# LED_ring.net
KiCad netlist of a schematic drawn in Altium Designer
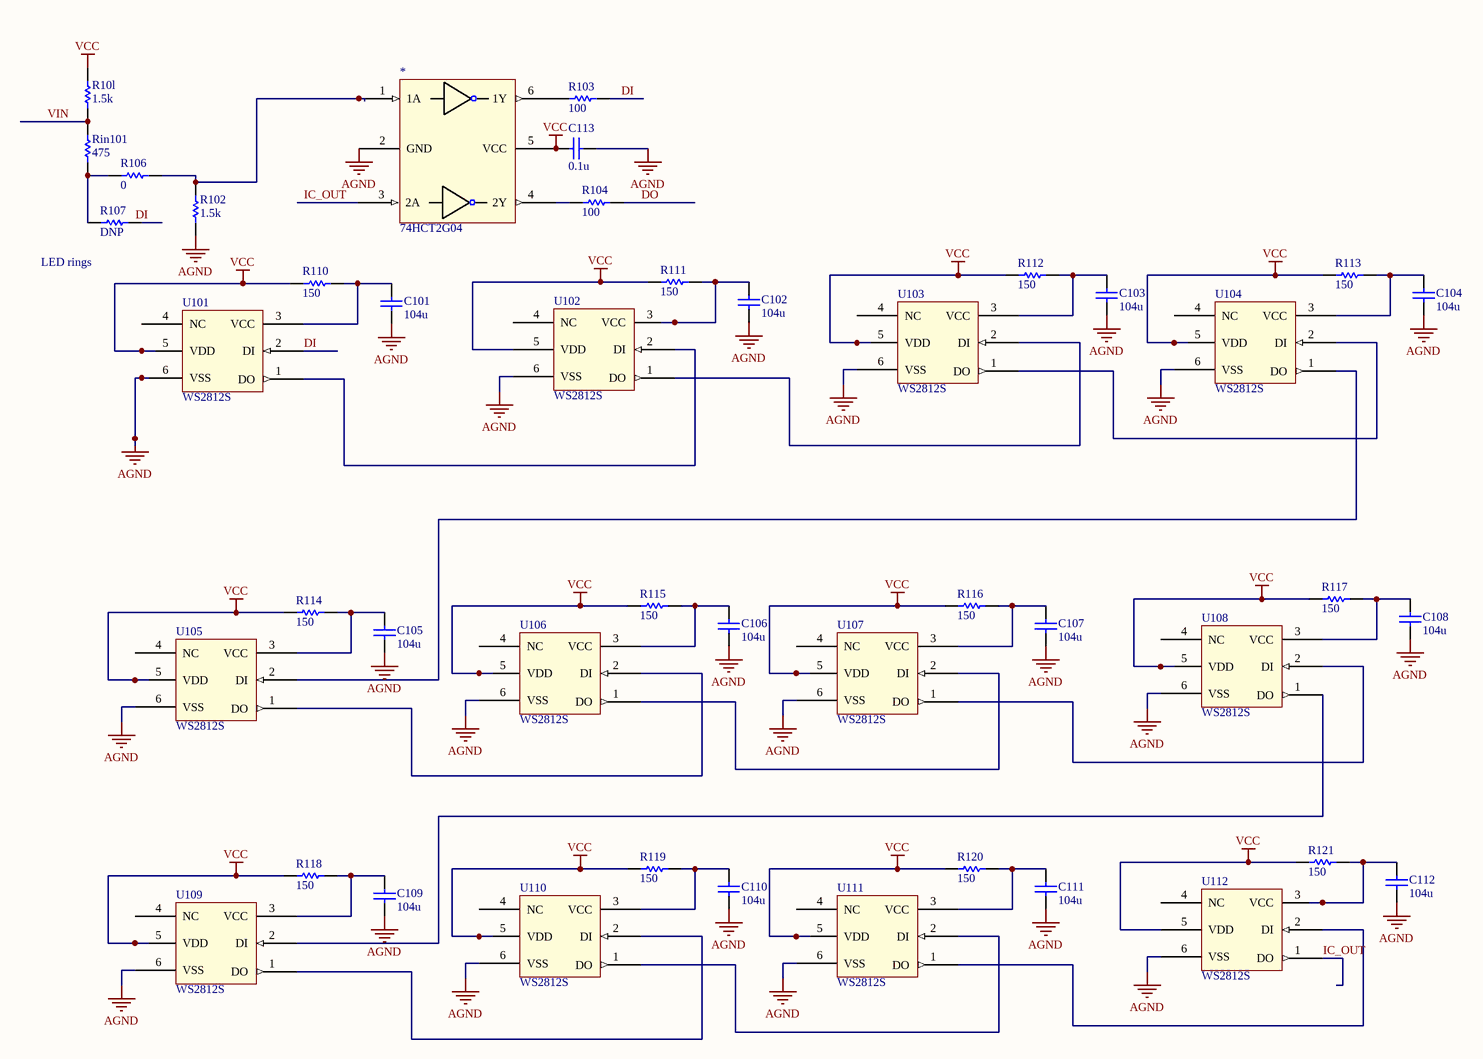
[diagram p0: LED_ring.SchDoc]

(export (version "E")
  (design (tool "Eeschema 10.0.6"))
  (components
    (comp (ref "*")
      (value "74HCT2G04")
      (footprint "SOT363-6M")
      (description "Dual inverter The 74HC2G04; 74HCT2G04 is a high-speed Si-gate CMOS device.")
      (libsource (lib "Hello") (part "74HCT2G04"))
    )
    (comp (ref "C101")
      (value "104u")
      (footprint "CAP0603_SENSE_DVT")
      (description "Chip capacitor")
      (fields (field (name "TOLERANCE") "10%") (field (name "VOLTAGE") "6.3V"))
      (libsource (lib "Hello") (part "C_10u_10_6.3_X5R_0603"))
    )
    (comp (ref "C102")
      (value "104u")
      (footprint "CAP0603_SENSE_DVT")
      (description "Chip capacitor")
      (fields (field (name "TOLERANCE") "10%") (field (name "VOLTAGE") "6.3V"))
      (libsource (lib "Hello") (part "C_10u_10_6.3_X5R_0603"))
    )
    (comp (ref "C103")
      (value "104u")
      (footprint "CAP0603_SENSE_DVT")
      (description "Chip capacitor")
      (fields (field (name "TOLERANCE") "10%") (field (name "VOLTAGE") "6.3V"))
      (libsource (lib "Hello") (part "C_10u_10_6.3_X5R_0603"))
    )
    (comp (ref "C104")
      (value "104u")
      (footprint "CAP0603_SENSE_DVT")
      (description "Chip capacitor")
      (fields (field (name "TOLERANCE") "10%") (field (name "VOLTAGE") "6.3V"))
      (libsource (lib "Hello") (part "C_10u_10_6.3_X5R_0603"))
    )
    (comp (ref "C105")
      (value "104u")
      (footprint "CAP0603_SENSE_DVT")
      (description "Chip capacitor")
      (fields (field (name "TOLERANCE") "10%") (field (name "VOLTAGE") "6.3V"))
      (libsource (lib "Hello") (part "C_10u_10_6.3_X5R_0603"))
    )
    (comp (ref "C106")
      (value "104u")
      (footprint "CAP0603_SENSE_DVT")
      (description "Chip capacitor")
      (fields (field (name "TOLERANCE") "10%") (field (name "VOLTAGE") "6.3V"))
      (libsource (lib "Hello") (part "C_10u_10_6.3_X5R_0603"))
    )
    (comp (ref "C107")
      (value "104u")
      (footprint "CAP0603_SENSE_DVT")
      (description "Chip capacitor")
      (fields (field (name "TOLERANCE") "10%") (field (name "VOLTAGE") "6.3V"))
      (libsource (lib "Hello") (part "C_10u_10_6.3_X5R_0603"))
    )
    (comp (ref "C108")
      (value "104u")
      (footprint "CAP0603_SENSE_DVT")
      (description "Chip capacitor")
      (fields (field (name "TOLERANCE") "10%") (field (name "VOLTAGE") "6.3V"))
      (libsource (lib "Hello") (part "C_10u_10_6.3_X5R_0603"))
    )
    (comp (ref "C109")
      (value "104u")
      (footprint "CAP0603_SENSE_DVT")
      (description "Chip capacitor")
      (fields (field (name "TOLERANCE") "10%") (field (name "VOLTAGE") "6.3V"))
      (libsource (lib "Hello") (part "C_10u_10_6.3_X5R_0603"))
    )
    (comp (ref "C110")
      (value "104u")
      (footprint "CAP0603_SENSE_DVT")
      (description "Chip capacitor")
      (fields (field (name "TOLERANCE") "10%") (field (name "VOLTAGE") "6.3V"))
      (libsource (lib "Hello") (part "C_10u_10_6.3_X5R_0603"))
    )
    (comp (ref "C111")
      (value "104u")
      (footprint "CAP0603_SENSE_DVT")
      (description "Chip capacitor")
      (fields (field (name "TOLERANCE") "10%") (field (name "VOLTAGE") "6.3V"))
      (libsource (lib "Hello") (part "C_10u_10_6.3_X5R_0603"))
    )
    (comp (ref "C112")
      (value "104u")
      (footprint "CAP0603_SENSE_DVT")
      (description "Chip capacitor")
      (fields (field (name "TOLERANCE") "10%") (field (name "VOLTAGE") "6.3V"))
      (libsource (lib "Hello") (part "C_10u_10_6.3_X5R_0603"))
    )
    (comp (ref "C113")
      (value "0.1u")
      (footprint "CAP0402_SENSE_DVT")
      (description "Chip capacitor")
      (fields (field (name "TOLERANCE") "10%") (field (name "VOLTAGE") "50V"))
      (libsource (lib "Hello") (part "C_0.1u_10_50_X7R_0402"))
    )
    (comp (ref "R10l")
      (value "1.5k")
      (footprint "RES0402_SENSE_DVT")
      (description "Chip Resistor")
      (fields (field (name "TOLERANCE") "5 %") (field (name "POWER") "0.1 W"))
      (libsource (lib "Hello") (part "R_1.5k_5_0.1_0402"))
    )
    (comp (ref "R102")
      (value "1.5k")
      (footprint "RES0402_SENSE_DVT")
      (description "Chip Resistor")
      (fields (field (name "TOLERANCE") "5 %") (field (name "POWER") "0.1 W"))
      (libsource (lib "Hello") (part "R_1.5k_5_0.1_0402"))
    )
    (comp (ref "R103")
      (value "100")
      (footprint "RES0402_SENSE_DVT")
      (description "Chip Resistor")
      (fields (field (name "TOLERANCE") "1 %") (field (name "POWER") "0.1 W"))
      (libsource (lib "Hello") (part "R_100_1_0.1_0402"))
    )
    (comp (ref "R104")
      (value "100")
      (footprint "RES0402_SENSE_DVT")
      (description "Chip Resistor")
      (fields (field (name "TOLERANCE") "1 %") (field (name "POWER") "0.1 W"))
      (libsource (lib "Hello") (part "R_100_1_0.1_0402"))
    )
    (comp (ref "R106")
      (value "0")
      (footprint "RES0402_SENSE_DVT")
      (description "Chip Resistor")
      (fields (field (name "TOLERANCE") "Jumper") (field (name "POWER") "0.1 W"))
      (libsource (lib "Hello") (part "R_0_jumper_0.1_0402"))
    )
    (comp (ref "R107")
      (value "DNP")
      (footprint "RES0402_SENSE_DVT")
      (description "Chip Resistor")
      (fields (field (name "TOLERANCE") "Jumper") (field (name "POWER") "0.1 W"))
      (libsource (lib "Hello") (part "R_0_jumper_0.1_0402"))
    )
    (comp (ref "R110")
      (value "150")
      (footprint "RES0402_SENSE_DVT")
      (description "Chip Resistor")
      (fields (field (name "TOLERANCE") "1 %") (field (name "POWER") "0.1 W"))
      (libsource (lib "Hello") (part "R_150_1_0.1_0402"))
    )
    (comp (ref "R111")
      (value "150")
      (footprint "RES0402_SENSE_DVT")
      (description "Chip Resistor")
      (fields (field (name "TOLERANCE") "1 %") (field (name "POWER") "0.1 W"))
      (libsource (lib "Hello") (part "R_150_1_0.1_0402"))
    )
    (comp (ref "R112")
      (value "150")
      (footprint "RES0402_SENSE_DVT")
      (description "Chip Resistor")
      (fields (field (name "TOLERANCE") "1 %") (field (name "POWER") "0.1 W"))
      (libsource (lib "Hello") (part "R_150_1_0.1_0402"))
    )
    (comp (ref "R113")
      (value "150")
      (footprint "RES0402_SENSE_DVT")
      (description "Chip Resistor")
      (fields (field (name "TOLERANCE") "1 %") (field (name "POWER") "0.1 W"))
      (libsource (lib "Hello") (part "R_150_1_0.1_0402"))
    )
    (comp (ref "R114")
      (value "150")
      (footprint "RES0402_SENSE_DVT")
      (description "Chip Resistor")
      (fields (field (name "TOLERANCE") "1 %") (field (name "POWER") "0.1 W"))
      (libsource (lib "Hello") (part "R_150_1_0.1_0402"))
    )
    (comp (ref "R115")
      (value "150")
      (footprint "RES0402_SENSE_DVT")
      (description "Chip Resistor")
      (fields (field (name "TOLERANCE") "1 %") (field (name "POWER") "0.1 W"))
      (libsource (lib "Hello") (part "R_150_1_0.1_0402"))
    )
    (comp (ref "R116")
      (value "150")
      (footprint "RES0402_SENSE_DVT")
      (description "Chip Resistor")
      (fields (field (name "TOLERANCE") "1 %") (field (name "POWER") "0.1 W"))
      (libsource (lib "Hello") (part "R_150_1_0.1_0402"))
    )
    (comp (ref "R117")
      (value "150")
      (footprint "RES0402_SENSE_DVT")
      (description "Chip Resistor")
      (fields (field (name "TOLERANCE") "1 %") (field (name "POWER") "0.1 W"))
      (libsource (lib "Hello") (part "R_150_1_0.1_0402"))
    )
    (comp (ref "R118")
      (value "150")
      (footprint "RES0402_SENSE_DVT")
      (description "Chip Resistor")
      (fields (field (name "TOLERANCE") "1 %") (field (name "POWER") "0.1 W"))
      (libsource (lib "Hello") (part "R_150_1_0.1_0402"))
    )
    (comp (ref "R119")
      (value "150")
      (footprint "RES0402_SENSE_DVT")
      (description "Chip Resistor")
      (fields (field (name "TOLERANCE") "1 %") (field (name "POWER") "0.1 W"))
      (libsource (lib "Hello") (part "R_150_1_0.1_0402"))
    )
    (comp (ref "R120")
      (value "150")
      (footprint "RES0402_SENSE_DVT")
      (description "Chip Resistor")
      (fields (field (name "TOLERANCE") "1 %") (field (name "POWER") "0.1 W"))
      (libsource (lib "Hello") (part "R_150_1_0.1_0402"))
    )
    (comp (ref "R121")
      (value "150")
      (footprint "RES0402_SENSE_DVT")
      (description "Chip Resistor")
      (fields (field (name "TOLERANCE") "1 %") (field (name "POWER") "0.1 W"))
      (libsource (lib "Hello") (part "R_150_1_0.1_0402"))
    )
    (comp (ref "Rin101")
      (value "475")
      (footprint "RES0402_SENSE_DVT")
      (description "Chip Resistor")
      (fields (field (name "TOLERANCE") "1 %") (field (name "POWER") "0.1 W"))
      (libsource (lib "Hello") (part "R_475_1_0.1_0402"))
    )
    (comp (ref "U101")
      (value "WS2812S")
      (footprint "6PIN_WS2812")
      (description "WS2812 Intelligent control LED integrated light source")
      (libsource (lib "Hello") (part "WS2812"))
    )
    (comp (ref "U102")
      (value "WS2812S")
      (footprint "6PIN_WS2812")
      (description "WS2812 Intelligent control LED integrated light source")
      (libsource (lib "Hello") (part "WS2812"))
    )
    (comp (ref "U103")
      (value "WS2812S")
      (footprint "6PIN_WS2812")
      (description "WS2812 Intelligent control LED integrated light source")
      (libsource (lib "Hello") (part "WS2812"))
    )
    (comp (ref "U104")
      (value "WS2812S")
      (footprint "6PIN_WS2812")
      (description "WS2812 Intelligent control LED integrated light source")
      (libsource (lib "Hello") (part "WS2812"))
    )
    (comp (ref "U105")
      (value "WS2812S")
      (footprint "6PIN_WS2812")
      (description "WS2812 Intelligent control LED integrated light source")
      (libsource (lib "Hello") (part "WS2812"))
    )
    (comp (ref "U106")
      (value "WS2812S")
      (footprint "6PIN_WS2812")
      (description "WS2812 Intelligent control LED integrated light source")
      (libsource (lib "Hello") (part "WS2812"))
    )
    (comp (ref "U107")
      (value "WS2812S")
      (footprint "6PIN_WS2812")
      (description "WS2812 Intelligent control LED integrated light source")
      (libsource (lib "Hello") (part "WS2812"))
    )
    (comp (ref "U108")
      (value "WS2812S")
      (footprint "6PIN_WS2812")
      (description "WS2812 Intelligent control LED integrated light source")
      (libsource (lib "Hello") (part "WS2812"))
    )
    (comp (ref "U109")
      (value "WS2812S")
      (footprint "6PIN_WS2812")
      (description "WS2812 Intelligent control LED integrated light source")
      (libsource (lib "Hello") (part "WS2812"))
    )
    (comp (ref "U110")
      (value "WS2812S")
      (footprint "6PIN_WS2812")
      (description "WS2812 Intelligent control LED integrated light source")
      (libsource (lib "Hello") (part "WS2812"))
    )
    (comp (ref "U111")
      (value "WS2812S")
      (footprint "6PIN_WS2812")
      (description "WS2812 Intelligent control LED integrated light source")
      (libsource (lib "Hello") (part "WS2812"))
    )
    (comp (ref "U112")
      (value "WS2812S")
      (footprint "6PIN_WS2812")
      (description "WS2812 Intelligent control LED integrated light source")
      (libsource (lib "Hello") (part "WS2812"))
    )
  )
  (nets
    (net (code "1") (name "/DI") (class "Default")
      (node (ref "R103") (pin "2") (pinfunction "2_2") (pintype "passive"))
      (node (ref "U101") (pin "2") (pinfunction "DI_2") (pintype "input"))
    )
    (net (code "2") (name "/DO") (class "Default")
      (node (ref "R104") (pin "2") (pinfunction "2_2") (pintype "passive"))
    )
    (net (code "3") (name "/IC_OUT") (class "Default")
      (node (ref "*") (pin "3") (pinfunction "2A_3") (pintype "input"))
      (node (ref "U112") (pin "1") (pinfunction "DO_1") (pintype "output"))
    )
    (net (code "4") (name "/VIN") (class "Default")
      (node (ref "R10l") (pin "1") (pinfunction "1_1") (pintype "passive"))
      (node (ref "Rin101") (pin "2") (pinfunction "2_2") (pintype "passive"))
    )
    (net (code "5") (name "AGND") (class "Default")
      (node (ref "*") (pin "2") (pinfunction "GND_2") (pintype "power_in"))
      (node (ref "C101") (pin "1") (pinfunction "1_1") (pintype "passive"))
      (node (ref "C102") (pin "1") (pinfunction "1_1") (pintype "passive"))
      (node (ref "C103") (pin "1") (pinfunction "1_1") (pintype "passive"))
      (node (ref "C104") (pin "1") (pinfunction "1_1") (pintype "passive"))
      (node (ref "C105") (pin "1") (pinfunction "1_1") (pintype "passive"))
      (node (ref "C106") (pin "1") (pinfunction "1_1") (pintype "passive"))
      (node (ref "C107") (pin "1") (pinfunction "1_1") (pintype "passive"))
      (node (ref "C108") (pin "1") (pinfunction "1_1") (pintype "passive"))
      (node (ref "C109") (pin "1") (pinfunction "1_1") (pintype "passive"))
      (node (ref "C110") (pin "1") (pinfunction "1_1") (pintype "passive"))
      (node (ref "C111") (pin "1") (pinfunction "1_1") (pintype "passive"))
      (node (ref "C112") (pin "1") (pinfunction "1_1") (pintype "passive"))
      (node (ref "C113") (pin "2") (pinfunction "2_2") (pintype "passive"))
      (node (ref "R102") (pin "1") (pinfunction "1_1") (pintype "passive"))
      (node (ref "U101") (pin "6") (pinfunction "VSS_6") (pintype "power_in"))
      (node (ref "U102") (pin "6") (pinfunction "VSS_6") (pintype "power_in"))
      (node (ref "U103") (pin "6") (pinfunction "VSS_6") (pintype "power_in"))
      (node (ref "U104") (pin "6") (pinfunction "VSS_6") (pintype "power_in"))
      (node (ref "U105") (pin "6") (pinfunction "VSS_6") (pintype "power_in"))
      (node (ref "U106") (pin "6") (pinfunction "VSS_6") (pintype "power_in"))
      (node (ref "U107") (pin "6") (pinfunction "VSS_6") (pintype "power_in"))
      (node (ref "U108") (pin "6") (pinfunction "VSS_6") (pintype "power_in"))
      (node (ref "U109") (pin "6") (pinfunction "VSS_6") (pintype "power_in"))
      (node (ref "U110") (pin "6") (pinfunction "VSS_6") (pintype "power_in"))
      (node (ref "U111") (pin "6") (pinfunction "VSS_6") (pintype "power_in"))
      (node (ref "U112") (pin "6") (pinfunction "VSS_6") (pintype "power_in"))
    )
    (net (code "6") (name "Net-(*-1A)") (class "Default")
      (node (ref "*") (pin "1") (pinfunction "1A_1") (pintype "input"))
      (node (ref "R102") (pin "2") (pinfunction "2_2") (pintype "passive"))
      (node (ref "R106") (pin "2") (pinfunction "2_2") (pintype "passive"))
    )
    (net (code "7") (name "Net-(*-1Y)") (class "Default")
      (node (ref "*") (pin "6") (pinfunction "1Y_6") (pintype "output"))
      (node (ref "R103") (pin "1") (pinfunction "1_1") (pintype "passive"))
    )
    (net (code "8") (name "Net-(*-2Y)") (class "Default")
      (node (ref "*") (pin "4") (pinfunction "2Y_4") (pintype "output"))
      (node (ref "R104") (pin "1") (pinfunction "1_1") (pintype "passive"))
    )
    (net (code "9") (name "Net-(R106-Pad1)") (class "Default")
      (node (ref "R106") (pin "1") (pinfunction "1_1") (pintype "passive"))
      (node (ref "R107") (pin "1") (pinfunction "1_1") (pintype "passive"))
      (node (ref "Rin101") (pin "1") (pinfunction "1_1") (pintype "passive"))
    )
    (net (code "10") (name "Net-(U101-DO)") (class "Default")
      (node (ref "U101") (pin "1") (pinfunction "DO_1") (pintype "output"))
      (node (ref "U102") (pin "2") (pinfunction "DI_2") (pintype "input"))
    )
    (net (code "11") (name "Net-(U101-VCC)") (class "Default")
      (node (ref "C101") (pin "2") (pinfunction "2_2") (pintype "passive"))
      (node (ref "R110") (pin "1") (pinfunction "1_1") (pintype "passive"))
      (node (ref "U101") (pin "3") (pinfunction "VCC_3") (pintype "power_in"))
    )
    (net (code "12") (name "Net-(U102-DO)") (class "Default")
      (node (ref "U102") (pin "1") (pinfunction "DO_1") (pintype "output"))
      (node (ref "U103") (pin "2") (pinfunction "DI_2") (pintype "input"))
    )
    (net (code "13") (name "Net-(U102-VCC)") (class "Default")
      (node (ref "C102") (pin "2") (pinfunction "2_2") (pintype "passive"))
      (node (ref "R111") (pin "1") (pinfunction "1_1") (pintype "passive"))
      (node (ref "U102") (pin "3") (pinfunction "VCC_3") (pintype "power_in"))
    )
    (net (code "14") (name "Net-(U103-DO)") (class "Default")
      (node (ref "U103") (pin "1") (pinfunction "DO_1") (pintype "output"))
      (node (ref "U104") (pin "2") (pinfunction "DI_2") (pintype "input"))
    )
    (net (code "15") (name "Net-(U103-VCC)") (class "Default")
      (node (ref "C103") (pin "2") (pinfunction "2_2") (pintype "passive"))
      (node (ref "R112") (pin "1") (pinfunction "1_1") (pintype "passive"))
      (node (ref "U103") (pin "3") (pinfunction "VCC_3") (pintype "power_in"))
    )
    (net (code "16") (name "Net-(U104-DO)") (class "Default")
      (node (ref "U104") (pin "1") (pinfunction "DO_1") (pintype "output"))
      (node (ref "U105") (pin "2") (pinfunction "DI_2") (pintype "input"))
    )
    (net (code "17") (name "Net-(U104-VCC)") (class "Default")
      (node (ref "C104") (pin "2") (pinfunction "2_2") (pintype "passive"))
      (node (ref "R113") (pin "1") (pinfunction "1_1") (pintype "passive"))
      (node (ref "U104") (pin "3") (pinfunction "VCC_3") (pintype "power_in"))
    )
    (net (code "18") (name "Net-(U105-DO)") (class "Default")
      (node (ref "U105") (pin "1") (pinfunction "DO_1") (pintype "output"))
      (node (ref "U106") (pin "2") (pinfunction "DI_2") (pintype "input"))
    )
    (net (code "19") (name "Net-(U105-VCC)") (class "Default")
      (node (ref "C105") (pin "2") (pinfunction "2_2") (pintype "passive"))
      (node (ref "R114") (pin "1") (pinfunction "1_1") (pintype "passive"))
      (node (ref "U105") (pin "3") (pinfunction "VCC_3") (pintype "power_in"))
    )
    (net (code "20") (name "Net-(U106-DO)") (class "Default")
      (node (ref "U106") (pin "1") (pinfunction "DO_1") (pintype "output"))
      (node (ref "U107") (pin "2") (pinfunction "DI_2") (pintype "input"))
    )
    (net (code "21") (name "Net-(U106-VCC)") (class "Default")
      (node (ref "C106") (pin "2") (pinfunction "2_2") (pintype "passive"))
      (node (ref "R115") (pin "1") (pinfunction "1_1") (pintype "passive"))
      (node (ref "U106") (pin "3") (pinfunction "VCC_3") (pintype "power_in"))
    )
    (net (code "22") (name "Net-(U107-DO)") (class "Default")
      (node (ref "U107") (pin "1") (pinfunction "DO_1") (pintype "output"))
      (node (ref "U108") (pin "2") (pinfunction "DI_2") (pintype "input"))
    )
    (net (code "23") (name "Net-(U107-VCC)") (class "Default")
      (node (ref "C107") (pin "2") (pinfunction "2_2") (pintype "passive"))
      (node (ref "R116") (pin "1") (pinfunction "1_1") (pintype "passive"))
      (node (ref "U107") (pin "3") (pinfunction "VCC_3") (pintype "power_in"))
    )
    (net (code "24") (name "Net-(U108-DO)") (class "Default")
      (node (ref "U108") (pin "1") (pinfunction "DO_1") (pintype "output"))
      (node (ref "U109") (pin "2") (pinfunction "DI_2") (pintype "input"))
    )
    (net (code "25") (name "Net-(U108-VCC)") (class "Default")
      (node (ref "C108") (pin "2") (pinfunction "2_2") (pintype "passive"))
      (node (ref "R117") (pin "1") (pinfunction "1_1") (pintype "passive"))
      (node (ref "U108") (pin "3") (pinfunction "VCC_3") (pintype "power_in"))
    )
    (net (code "26") (name "Net-(U109-DO)") (class "Default")
      (node (ref "U109") (pin "1") (pinfunction "DO_1") (pintype "output"))
      (node (ref "U110") (pin "2") (pinfunction "DI_2") (pintype "input"))
    )
    (net (code "27") (name "Net-(U109-VCC)") (class "Default")
      (node (ref "C109") (pin "2") (pinfunction "2_2") (pintype "passive"))
      (node (ref "R118") (pin "1") (pinfunction "1_1") (pintype "passive"))
      (node (ref "U109") (pin "3") (pinfunction "VCC_3") (pintype "power_in"))
    )
    (net (code "28") (name "Net-(U110-DO)") (class "Default")
      (node (ref "U110") (pin "1") (pinfunction "DO_1") (pintype "output"))
      (node (ref "U111") (pin "2") (pinfunction "DI_2") (pintype "input"))
    )
    (net (code "29") (name "Net-(U110-VCC)") (class "Default")
      (node (ref "C110") (pin "2") (pinfunction "2_2") (pintype "passive"))
      (node (ref "R119") (pin "1") (pinfunction "1_1") (pintype "passive"))
      (node (ref "U110") (pin "3") (pinfunction "VCC_3") (pintype "power_in"))
    )
    (net (code "30") (name "Net-(U111-DO)") (class "Default")
      (node (ref "U111") (pin "1") (pinfunction "DO_1") (pintype "output"))
      (node (ref "U112") (pin "2") (pinfunction "DI_2") (pintype "input"))
    )
    (net (code "31") (name "Net-(U111-VCC)") (class "Default")
      (node (ref "C111") (pin "2") (pinfunction "2_2") (pintype "passive"))
      (node (ref "R120") (pin "1") (pinfunction "1_1") (pintype "passive"))
      (node (ref "U111") (pin "3") (pinfunction "VCC_3") (pintype "power_in"))
    )
    (net (code "32") (name "Net-(U112-VCC)") (class "Default")
      (node (ref "C112") (pin "2") (pinfunction "2_2") (pintype "passive"))
      (node (ref "R121") (pin "1") (pinfunction "1_1") (pintype "passive"))
      (node (ref "U112") (pin "3") (pinfunction "VCC_3") (pintype "power_in"))
    )
    (net (code "33") (name "VCC") (class "Default")
      (node (ref "*") (pin "5") (pinfunction "VCC_5") (pintype "power_in"))
      (node (ref "C113") (pin "1") (pinfunction "1_1") (pintype "passive"))
      (node (ref "R10l") (pin "2") (pinfunction "2_2") (pintype "passive"))
      (node (ref "R110") (pin "2") (pinfunction "2_2") (pintype "passive"))
      (node (ref "R111") (pin "2") (pinfunction "2_2") (pintype "passive"))
      (node (ref "R112") (pin "2") (pinfunction "2_2") (pintype "passive"))
      (node (ref "R113") (pin "2") (pinfunction "2_2") (pintype "passive"))
      (node (ref "R114") (pin "2") (pinfunction "2_2") (pintype "passive"))
      (node (ref "R115") (pin "2") (pinfunction "2_2") (pintype "passive"))
      (node (ref "R116") (pin "2") (pinfunction "2_2") (pintype "passive"))
      (node (ref "R117") (pin "2") (pinfunction "2_2") (pintype "passive"))
      (node (ref "R118") (pin "2") (pinfunction "2_2") (pintype "passive"))
      (node (ref "R119") (pin "2") (pinfunction "2_2") (pintype "passive"))
      (node (ref "R120") (pin "2") (pinfunction "2_2") (pintype "passive"))
      (node (ref "R121") (pin "2") (pinfunction "2_2") (pintype "passive"))
      (node (ref "U101") (pin "5") (pinfunction "VDD_5") (pintype "power_in"))
      (node (ref "U102") (pin "5") (pinfunction "VDD_5") (pintype "power_in"))
      (node (ref "U103") (pin "5") (pinfunction "VDD_5") (pintype "power_in"))
      (node (ref "U104") (pin "5") (pinfunction "VDD_5") (pintype "power_in"))
      (node (ref "U105") (pin "5") (pinfunction "VDD_5") (pintype "power_in"))
      (node (ref "U106") (pin "5") (pinfunction "VDD_5") (pintype "power_in"))
      (node (ref "U107") (pin "5") (pinfunction "VDD_5") (pintype "power_in"))
      (node (ref "U108") (pin "5") (pinfunction "VDD_5") (pintype "power_in"))
      (node (ref "U109") (pin "5") (pinfunction "VDD_5") (pintype "power_in"))
      (node (ref "U110") (pin "5") (pinfunction "VDD_5") (pintype "power_in"))
      (node (ref "U111") (pin "5") (pinfunction "VDD_5") (pintype "power_in"))
      (node (ref "U112") (pin "5") (pinfunction "VDD_5") (pintype "power_in"))
    )
    (net (code "34") (name "unconnected-(R107-Pad2)") (class "Default")
      (node (ref "R107") (pin "2") (pinfunction "2_2") (pintype "passive"))
    )
    (net (code "35") (name "unconnected-(U101-NC-Pad4)") (class "Default")
      (node (ref "U101") (pin "4") (pinfunction "NC_4") (pintype "passive"))
    )
    (net (code "36") (name "unconnected-(U102-NC-Pad4)") (class "Default")
      (node (ref "U102") (pin "4") (pinfunction "NC_4") (pintype "passive"))
    )
    (net (code "37") (name "unconnected-(U103-NC-Pad4)") (class "Default")
      (node (ref "U103") (pin "4") (pinfunction "NC_4") (pintype "passive"))
    )
    (net (code "38") (name "unconnected-(U104-NC-Pad4)") (class "Default")
      (node (ref "U104") (pin "4") (pinfunction "NC_4") (pintype "passive"))
    )
    (net (code "39") (name "unconnected-(U105-NC-Pad4)") (class "Default")
      (node (ref "U105") (pin "4") (pinfunction "NC_4") (pintype "passive"))
    )
    (net (code "40") (name "unconnected-(U106-NC-Pad4)") (class "Default")
      (node (ref "U106") (pin "4") (pinfunction "NC_4") (pintype "passive"))
    )
    (net (code "41") (name "unconnected-(U107-NC-Pad4)") (class "Default")
      (node (ref "U107") (pin "4") (pinfunction "NC_4") (pintype "passive"))
    )
    (net (code "42") (name "unconnected-(U108-NC-Pad4)") (class "Default")
      (node (ref "U108") (pin "4") (pinfunction "NC_4") (pintype "passive"))
    )
    (net (code "43") (name "unconnected-(U109-NC-Pad4)") (class "Default")
      (node (ref "U109") (pin "4") (pinfunction "NC_4") (pintype "passive"))
    )
    (net (code "44") (name "unconnected-(U110-NC-Pad4)") (class "Default")
      (node (ref "U110") (pin "4") (pinfunction "NC_4") (pintype "passive"))
    )
    (net (code "45") (name "unconnected-(U111-NC-Pad4)") (class "Default")
      (node (ref "U111") (pin "4") (pinfunction "NC_4") (pintype "passive"))
    )
    (net (code "46") (name "unconnected-(U112-NC-Pad4)") (class "Default")
      (node (ref "U112") (pin "4") (pinfunction "NC_4") (pintype "passive"))
    )
  )
)
